# Display.net
KiCad netlist of a schematic drawn in EAGLE
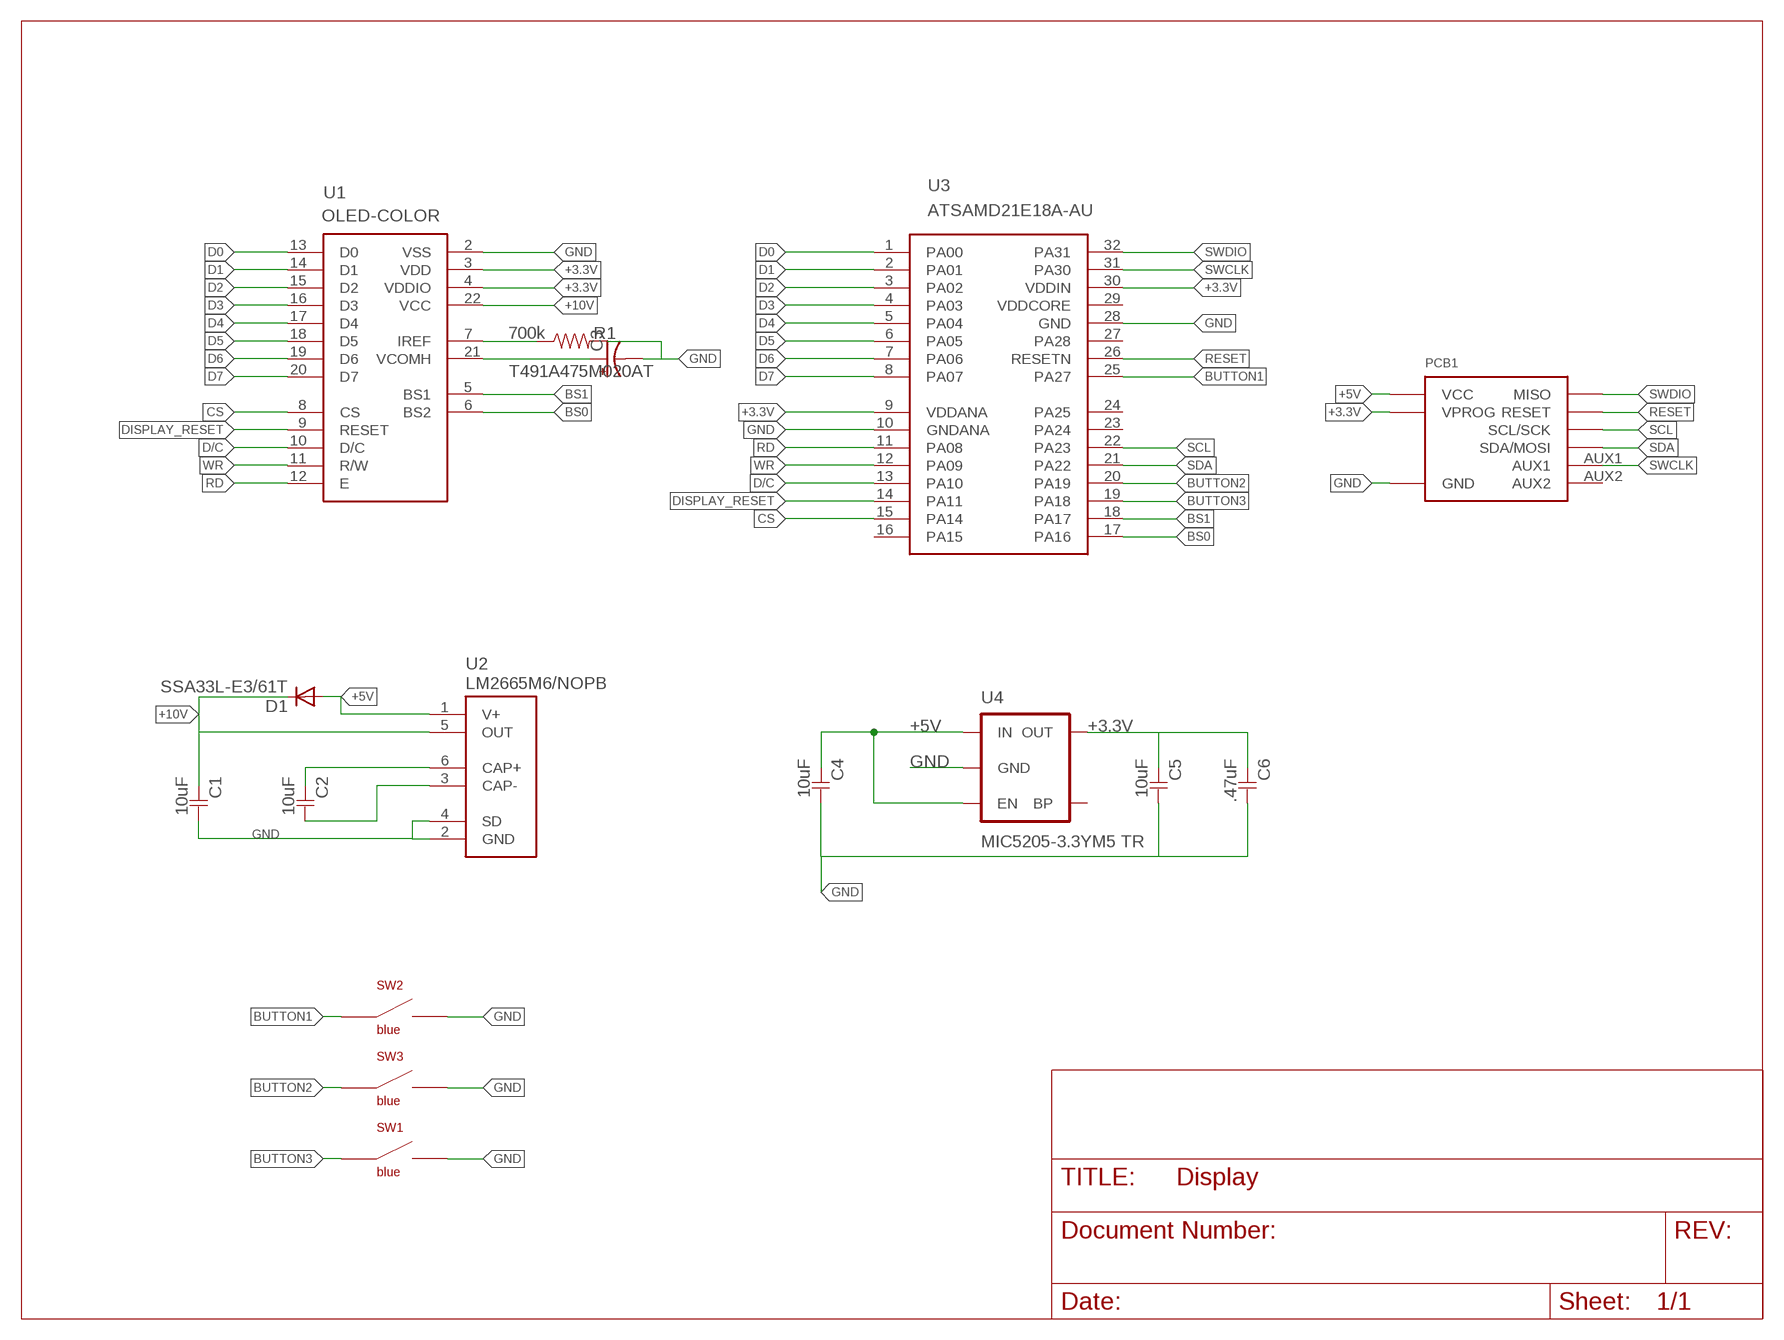
[diagram p0: schematic, sheet 1]

(export (version "E")
  (design (tool "Eeschema 10.0.6"))
  (components
    (comp (ref "C1")
      (value "10uF")
      (footprint "eagle-import:0805")
      (libsource (lib "eagle-import") (part "CAPACITOR"))
    )
    (comp (ref "C2")
      (value "10uF")
      (footprint "eagle-import:0805")
      (libsource (lib "eagle-import") (part "CAPACITOR"))
    )
    (comp (ref "C3")
      (value "T491A475M020AT")
      (footprint "eagle-import:EIA3216")
      (libsource (lib "eagle-import") (part "10UF-16V-10%(TANT)"))
    )
    (comp (ref "C4")
      (value "10uF")
      (footprint "eagle-import:0805")
      (libsource (lib "eagle-import") (part "CAPACITOR"))
    )
    (comp (ref "C5")
      (value "10uF")
      (footprint "eagle-import:0805")
      (libsource (lib "eagle-import") (part "CAPACITOR"))
    )
    (comp (ref "C6")
      (value ".47uF")
      (footprint "eagle-import:0805")
      (libsource (lib "eagle-import") (part "CAPACITOR"))
    )
    (comp (ref "D1")
      (value "SSA33L-E3/61T")
      (footprint "eagle-import:SMA-DIODE")
      (libsource (lib "eagle-import") (part "DIODESMA"))
    )
    (comp (ref "PCB1")
      (value "MAGDEVICE-V2-OLED")
      (footprint "eagle-import:MAGDEVICE-V2-OLED")
      (fields (field (name "BOARD") "Display") (field (name "VERSION") "2"))
      (libsource (lib "eagle-import") (part "MAGDEVICE-V2-OLED"))
    )
    (comp (ref "R1")
      (value "700k")
      (footprint "eagle-import:0805")
      (libsource (lib "eagle-import") (part "RESISTOR"))
    )
    (comp (ref "SW1")
      (value "blue")
      (footprint "eagle-import:BOURNS-7914J")
      (fields (field (name "PARTNUM") "7914J-1-000E"))
      (libsource (lib "eagle-import") (part "SWITCHBOURNS-7914J"))
    )
    (comp (ref "SW2")
      (value "blue")
      (footprint "eagle-import:BOURNS-7914J")
      (fields (field (name "PARTNUM") "7914J-1-000E"))
      (libsource (lib "eagle-import") (part "SWITCHBOURNS-7914J"))
    )
    (comp (ref "SW3")
      (value "blue")
      (footprint "eagle-import:BOURNS-7914J")
      (fields (field (name "PARTNUM") "7914J-1-000E"))
      (libsource (lib "eagle-import") (part "SWITCHBOURNS-7914J"))
    )
    (comp (ref "U1")
      (value "OLED-COLOR")
      (footprint "eagle-import:FPC-24")
      (libsource (lib "eagle-import") (part "OLED-COLOR"))
    )
    (comp (ref "U2")
      (value "LM2665M6/NOPB")
      (footprint "eagle-import:SOT-26")
      (libsource (lib "eagle-import") (part "LM2665"))
    )
    (comp (ref "U3")
      (value "ATSAMD21E18A-AU")
      (footprint "eagle-import:TQFP-32")
      (libsource (lib "eagle-import") (part "SAMD21E"))
    )
    (comp (ref "U4")
      (value "MIC5205-3.3YM5 TR")
      (footprint "eagle-import:SOT23-5")
      (libsource (lib "eagle-import") (part "VREG-MIC5205-3.3V"))
    )
  )
  (nets
    (net (code "1") (name "+3.3V") (class "Default")
      (node (ref "C5") (pin "1") (pinfunction "1_1") (pintype "passive"))
      (node (ref "C6") (pin "1") (pinfunction "1_1") (pintype "passive"))
      (node (ref "PCB1") (pin "VPROG") (pinfunction "VPROG_VPROG") (pintype "bidirectional"))
      (node (ref "U1") (pin "3") (pinfunction "VDD_3") (pintype "bidirectional"))
      (node (ref "U1") (pin "4") (pinfunction "VDDIO_4") (pintype "bidirectional"))
      (node (ref "U3") (pin "30") (pinfunction "VDDIN_30") (pintype "bidirectional"))
      (node (ref "U3") (pin "9") (pinfunction "VDDANA_9") (pintype "bidirectional"))
      (node (ref "U4") (pin "5") (pinfunction "OUT_5") (pintype "passive"))
    )
    (net (code "2") (name "+5V") (class "Default")
      (node (ref "C4") (pin "1") (pinfunction "1_1") (pintype "passive"))
      (node (ref "D1") (pin "A") (pinfunction "A_A") (pintype "passive"))
      (node (ref "PCB1") (pin "VCC") (pinfunction "VCC_VCC") (pintype "bidirectional"))
      (node (ref "U2") (pin "1") (pinfunction "V+_1") (pintype "bidirectional"))
      (node (ref "U4") (pin "1") (pinfunction "IN_1") (pintype "input"))
      (node (ref "U4") (pin "3") (pinfunction "EN_3") (pintype "input"))
    )
    (net (code "3") (name "+10V") (class "Default")
      (node (ref "C1") (pin "1") (pinfunction "1_1") (pintype "passive"))
      (node (ref "D1") (pin "C") (pinfunction "C_C") (pintype "passive"))
      (node (ref "U1") (pin "22") (pinfunction "VCC_22") (pintype "bidirectional"))
      (node (ref "U2") (pin "5") (pinfunction "OUT_5") (pintype "bidirectional"))
    )
    (net (code "4") (name "BS0") (class "Default")
      (node (ref "U1") (pin "6") (pinfunction "BS2_6") (pintype "bidirectional"))
      (node (ref "U3") (pin "17") (pinfunction "PA16_17") (pintype "bidirectional"))
    )
    (net (code "5") (name "BS1") (class "Default")
      (node (ref "U1") (pin "5") (pinfunction "BS1_5") (pintype "bidirectional"))
      (node (ref "U3") (pin "18") (pinfunction "PA17_18") (pintype "bidirectional"))
    )
    (net (code "6") (name "BUTTON1") (class "Default")
      (node (ref "SW2") (pin "POS$1") (pinfunction "POS1_POS$1") (pintype "bidirectional"))
      (node (ref "SW2") (pin "POS$2") (pinfunction "POS1_POS$2") (pintype "bidirectional"))
      (node (ref "U3") (pin "25") (pinfunction "PA27_25") (pintype "bidirectional"))
    )
    (net (code "7") (name "BUTTON2") (class "Default")
      (node (ref "SW3") (pin "POS$1") (pinfunction "POS1_POS$1") (pintype "bidirectional"))
      (node (ref "SW3") (pin "POS$2") (pinfunction "POS1_POS$2") (pintype "bidirectional"))
      (node (ref "U3") (pin "20") (pinfunction "PA19_20") (pintype "bidirectional"))
    )
    (net (code "8") (name "BUTTON3") (class "Default")
      (node (ref "SW1") (pin "POS$1") (pinfunction "POS1_POS$1") (pintype "bidirectional"))
      (node (ref "SW1") (pin "POS$2") (pinfunction "POS1_POS$2") (pintype "bidirectional"))
      (node (ref "U3") (pin "19") (pinfunction "PA18_19") (pintype "bidirectional"))
    )
    (net (code "9") (name "CS") (class "Default")
      (node (ref "U1") (pin "8") (pinfunction "CS_8") (pintype "bidirectional"))
      (node (ref "U3") (pin "15") (pinfunction "PA14_15") (pintype "bidirectional"))
    )
    (net (code "10") (name "D0") (class "Default")
      (node (ref "U1") (pin "13") (pinfunction "D0_13") (pintype "bidirectional"))
      (node (ref "U3") (pin "1") (pinfunction "PA00_1") (pintype "bidirectional"))
    )
    (net (code "11") (name "D1") (class "Default")
      (node (ref "U1") (pin "14") (pinfunction "D1_14") (pintype "bidirectional"))
      (node (ref "U3") (pin "2") (pinfunction "PA01_2") (pintype "bidirectional"))
    )
    (net (code "12") (name "D2") (class "Default")
      (node (ref "U1") (pin "15") (pinfunction "D2_15") (pintype "bidirectional"))
      (node (ref "U3") (pin "3") (pinfunction "PA02_3") (pintype "bidirectional"))
    )
    (net (code "13") (name "D3") (class "Default")
      (node (ref "U1") (pin "16") (pinfunction "D3_16") (pintype "bidirectional"))
      (node (ref "U3") (pin "4") (pinfunction "PA03_4") (pintype "bidirectional"))
    )
    (net (code "14") (name "D4") (class "Default")
      (node (ref "U1") (pin "17") (pinfunction "D4_17") (pintype "bidirectional"))
      (node (ref "U3") (pin "5") (pinfunction "PA04_5") (pintype "bidirectional"))
    )
    (net (code "15") (name "D5") (class "Default")
      (node (ref "U1") (pin "18") (pinfunction "D5_18") (pintype "bidirectional"))
      (node (ref "U3") (pin "6") (pinfunction "PA05_6") (pintype "bidirectional"))
    )
    (net (code "16") (name "D6") (class "Default")
      (node (ref "U1") (pin "19") (pinfunction "D6_19") (pintype "bidirectional"))
      (node (ref "U3") (pin "7") (pinfunction "PA06_7") (pintype "bidirectional"))
    )
    (net (code "17") (name "D7") (class "Default")
      (node (ref "U1") (pin "20") (pinfunction "D7_20") (pintype "bidirectional"))
      (node (ref "U3") (pin "8") (pinfunction "PA07_8") (pintype "bidirectional"))
    )
    (net (code "18") (name "DISPLAY_RESET") (class "Default")
      (node (ref "U1") (pin "9") (pinfunction "RESET_9") (pintype "bidirectional"))
      (node (ref "U3") (pin "14") (pinfunction "PA11_14") (pintype "bidirectional"))
    )
    (net (code "19") (name "D{slash}C") (class "Default")
      (node (ref "U1") (pin "10") (pinfunction "D/C_10") (pintype "bidirectional"))
      (node (ref "U3") (pin "13") (pinfunction "PA10_13") (pintype "bidirectional"))
    )
    (net (code "20") (name "GND") (class "Default")
      (node (ref "C1") (pin "2") (pinfunction "2_2") (pintype "passive"))
      (node (ref "C3") (pin "C") (pinfunction "-_C") (pintype "passive"))
      (node (ref "C4") (pin "2") (pinfunction "2_2") (pintype "passive"))
      (node (ref "C5") (pin "2") (pinfunction "2_2") (pintype "passive"))
      (node (ref "C6") (pin "2") (pinfunction "2_2") (pintype "passive"))
      (node (ref "PCB1") (pin "GND") (pinfunction "GND_GND") (pintype "bidirectional"))
      (node (ref "R1") (pin "2") (pinfunction "2_2") (pintype "passive"))
      (node (ref "SW1") (pin "NEG$1") (pinfunction "NEG1_NEG$1") (pintype "bidirectional"))
      (node (ref "SW1") (pin "NEG$2") (pinfunction "NEG1_NEG$2") (pintype "bidirectional"))
      (node (ref "SW2") (pin "NEG$1") (pinfunction "NEG1_NEG$1") (pintype "bidirectional"))
      (node (ref "SW2") (pin "NEG$2") (pinfunction "NEG1_NEG$2") (pintype "bidirectional"))
      (node (ref "SW3") (pin "NEG$1") (pinfunction "NEG1_NEG$1") (pintype "bidirectional"))
      (node (ref "SW3") (pin "NEG$2") (pinfunction "NEG1_NEG$2") (pintype "bidirectional"))
      (node (ref "U1") (pin "2") (pinfunction "VSS_2") (pintype "bidirectional"))
      (node (ref "U2") (pin "2") (pinfunction "GND_2") (pintype "bidirectional"))
      (node (ref "U2") (pin "4") (pinfunction "SD_4") (pintype "bidirectional"))
      (node (ref "U3") (pin "10") (pinfunction "GNDANA_10") (pintype "bidirectional"))
      (node (ref "U3") (pin "28") (pinfunction "GND_28") (pintype "bidirectional"))
      (node (ref "U4") (pin "2") (pinfunction "GND_2") (pintype "input"))
    )
    (net (code "21") (name "Net-(C3-+)") (class "Default")
      (node (ref "C3") (pin "A") (pinfunction "+_A") (pintype "passive"))
      (node (ref "U1") (pin "21") (pinfunction "VCOMH_21") (pintype "bidirectional"))
    )
    (net (code "22") (name "Net-(U1-IREF)") (class "Default")
      (node (ref "R1") (pin "1") (pinfunction "1_1") (pintype "passive"))
      (node (ref "U1") (pin "7") (pinfunction "IREF_7") (pintype "bidirectional"))
    )
    (net (code "23") (name "Net-(U2-CAP+)") (class "Default")
      (node (ref "C2") (pin "1") (pinfunction "1_1") (pintype "passive"))
      (node (ref "U2") (pin "6") (pinfunction "CAP+_6") (pintype "bidirectional"))
    )
    (net (code "24") (name "Net-(U2-CAP-)") (class "Default")
      (node (ref "C2") (pin "2") (pinfunction "2_2") (pintype "passive"))
      (node (ref "U2") (pin "3") (pinfunction "CAP-_3") (pintype "bidirectional"))
    )
    (net (code "25") (name "RD") (class "Default")
      (node (ref "U1") (pin "12") (pinfunction "E_12") (pintype "bidirectional"))
      (node (ref "U3") (pin "11") (pinfunction "PA08_11") (pintype "bidirectional"))
    )
    (net (code "26") (name "RESET") (class "Default")
      (node (ref "PCB1") (pin "RESET") (pinfunction "RESET_RESET") (pintype "bidirectional"))
      (node (ref "U3") (pin "26") (pinfunction "RESETN_26") (pintype "bidirectional"))
    )
    (net (code "27") (name "SCL") (class "Default")
      (node (ref "PCB1") (pin "SCL") (pinfunction "SCL/SCK_SCL") (pintype "bidirectional"))
      (node (ref "U3") (pin "22") (pinfunction "PA23_22") (pintype "bidirectional"))
    )
    (net (code "28") (name "SDA") (class "Default")
      (node (ref "PCB1") (pin "SDA") (pinfunction "SDA/MOSI_SDA") (pintype "bidirectional"))
      (node (ref "U3") (pin "21") (pinfunction "PA22_21") (pintype "bidirectional"))
    )
    (net (code "29") (name "SWCLK") (class "Default")
      (node (ref "PCB1") (pin "AUX1") (pinfunction "AUX1_AUX1") (pintype "bidirectional"))
      (node (ref "U3") (pin "31") (pinfunction "PA30_31") (pintype "bidirectional"))
    )
    (net (code "30") (name "SWDIO") (class "Default")
      (node (ref "PCB1") (pin "MISO") (pinfunction "MISO_MISO") (pintype "bidirectional"))
      (node (ref "U3") (pin "32") (pinfunction "PA31_32") (pintype "bidirectional"))
    )
    (net (code "31") (name "WR") (class "Default")
      (node (ref "U1") (pin "11") (pinfunction "R/W_11") (pintype "bidirectional"))
      (node (ref "U3") (pin "12") (pinfunction "PA09_12") (pintype "bidirectional"))
    )
    (net (code "32") (name "unconnected-(PCB1-PadAUX2)") (class "Default")
      (node (ref "PCB1") (pin "AUX2") (pinfunction "AUX2_AUX2") (pintype "bidirectional"))
    )
    (net (code "33") (name "unconnected-(U3-PA15-Pad16)") (class "Default")
      (node (ref "U3") (pin "16") (pinfunction "PA15_16") (pintype "bidirectional"))
    )
    (net (code "34") (name "unconnected-(U3-PA24-Pad23)") (class "Default")
      (node (ref "U3") (pin "23") (pinfunction "PA24_23") (pintype "bidirectional"))
    )
    (net (code "35") (name "unconnected-(U3-PA25-Pad24)") (class "Default")
      (node (ref "U3") (pin "24") (pinfunction "PA25_24") (pintype "bidirectional"))
    )
    (net (code "36") (name "unconnected-(U3-PA28-Pad27)") (class "Default")
      (node (ref "U3") (pin "27") (pinfunction "PA28_27") (pintype "bidirectional"))
    )
    (net (code "37") (name "unconnected-(U3-VDDCORE-Pad29)") (class "Default")
      (node (ref "U3") (pin "29") (pinfunction "VDDCORE_29") (pintype "bidirectional"))
    )
    (net (code "38") (name "unconnected-(U4-BP-Pad4)") (class "Default")
      (node (ref "U4") (pin "4") (pinfunction "BP_4") (pintype "input"))
    )
  )
)
